# preamp_duo.net
KiCad netlist of a schematic drawn in EAGLE
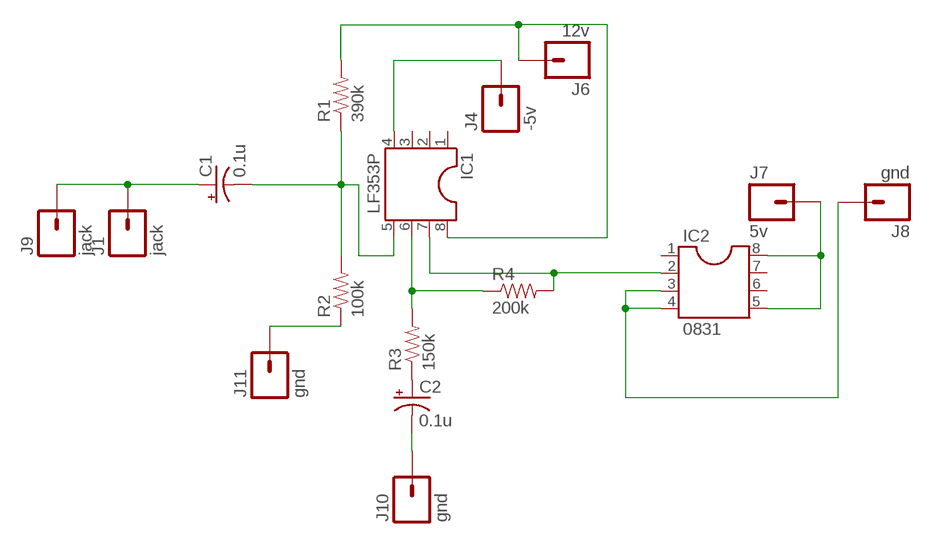
[diagram p0: schematic, sheet 1]

(export (version "E")
  (design (tool "Eeschema 10.0.6"))
  (components
    (comp (ref "C1")
      (value "0.1u")
      (footprint "eagle-import:CPOL-RADIAL-10UF-25V")
      (libsource (lib "eagle-import") (part "CAP_POLPTH2"))
    )
    (comp (ref "C2")
      (value "0.1u")
      (footprint "eagle-import:CPOL-RADIAL-10UF-25V")
      (libsource (lib "eagle-import") (part "CAP_POLPTH2"))
    )
    (comp (ref "IC1")
      (value "LF353P")
      (footprint "eagle-import:DIL08")
      (libsource (lib "eagle-import") (part "DIL8"))
    )
    (comp (ref "IC2")
      (value "0831")
      (footprint "eagle-import:DIL08")
      (libsource (lib "eagle-import") (part "DIL8"))
    )
    (comp (ref "J1")
      (value "jack")
      (footprint "eagle-import:1X01")
      (libsource (lib "eagle-import") (part "M01PTH"))
    )
    (comp (ref "J4")
      (value "-5v")
      (footprint "eagle-import:1X01")
      (libsource (lib "eagle-import") (part "M01PTH"))
    )
    (comp (ref "J6")
      (value "12v")
      (footprint "eagle-import:1X01")
      (libsource (lib "eagle-import") (part "M01PTH"))
    )
    (comp (ref "J7")
      (value "5v")
      (footprint "eagle-import:1X01")
      (libsource (lib "eagle-import") (part "M01PTH"))
    )
    (comp (ref "J8")
      (value "gnd")
      (footprint "eagle-import:1X01")
      (libsource (lib "eagle-import") (part "M01PTH"))
    )
    (comp (ref "J9")
      (value "jack")
      (footprint "eagle-import:1X01")
      (libsource (lib "eagle-import") (part "M01PTH"))
    )
    (comp (ref "J10")
      (value "gnd")
      (footprint "eagle-import:1X01")
      (libsource (lib "eagle-import") (part "M01PTH"))
    )
    (comp (ref "J11")
      (value "gnd")
      (footprint "eagle-import:1X01")
      (libsource (lib "eagle-import") (part "M01PTH"))
    )
    (comp (ref "R1")
      (value "390k")
      (footprint "eagle-import:AXIAL-0.3")
      (libsource (lib "eagle-import") (part "RESISTORAXIAL-0.3"))
    )
    (comp (ref "R2")
      (value "100k")
      (footprint "eagle-import:AXIAL-0.3")
      (libsource (lib "eagle-import") (part "RESISTORAXIAL-0.3"))
    )
    (comp (ref "R3")
      (value "150k")
      (footprint "eagle-import:AXIAL-0.3")
      (libsource (lib "eagle-import") (part "RESISTORAXIAL-0.3"))
    )
    (comp (ref "R4")
      (value "200k")
      (footprint "eagle-import:AXIAL-0.3")
      (libsource (lib "eagle-import") (part "RESISTORAXIAL-0.3"))
    )
  )
  (nets
    (net (code "1") (name "Net-(C1-+)") (class "Default")
      (node (ref "C1") (pin "1") (pinfunction "+_1") (pintype "passive"))
      (node (ref "J1") (pin "1") (pinfunction "1_1") (pintype "passive"))
      (node (ref "J9") (pin "1") (pinfunction "1_1") (pintype "passive"))
    )
    (net (code "2") (name "Net-(C1--)") (class "Default")
      (node (ref "C1") (pin "2") (pinfunction "-_2") (pintype "passive"))
      (node (ref "IC1") (pin "5") (pinfunction "5_5") (pintype "passive"))
      (node (ref "R1") (pin "P$1") (pinfunction "1_P$1") (pintype "passive"))
      (node (ref "R2") (pin "P$2") (pinfunction "2_P$2") (pintype "passive"))
    )
    (net (code "3") (name "Net-(C2-+)") (class "Default")
      (node (ref "C2") (pin "1") (pinfunction "+_1") (pintype "passive"))
      (node (ref "R3") (pin "P$1") (pinfunction "1_P$1") (pintype "passive"))
    )
    (net (code "4") (name "Net-(C2--)") (class "Default")
      (node (ref "C2") (pin "2") (pinfunction "-_2") (pintype "passive"))
      (node (ref "J10") (pin "1") (pinfunction "1_1") (pintype "passive"))
    )
    (net (code "5") (name "Net-(IC1-Pad4)") (class "Default")
      (node (ref "IC1") (pin "4") (pinfunction "4_4") (pintype "passive"))
      (node (ref "J4") (pin "1") (pinfunction "1_1") (pintype "passive"))
    )
    (net (code "6") (name "Net-(IC2-Pad3)") (class "Default")
      (node (ref "IC2") (pin "3") (pinfunction "3_3") (pintype "passive"))
      (node (ref "IC2") (pin "4") (pinfunction "4_4") (pintype "passive"))
      (node (ref "J8") (pin "1") (pinfunction "1_1") (pintype "passive"))
    )
    (net (code "7") (name "Net-(IC2-Pad5)") (class "Default")
      (node (ref "IC2") (pin "5") (pinfunction "5_5") (pintype "passive"))
      (node (ref "IC2") (pin "8") (pinfunction "8_8") (pintype "passive"))
      (node (ref "J7") (pin "1") (pinfunction "1_1") (pintype "passive"))
    )
    (net (code "8") (name "Net-(R1-2)") (class "Default")
      (node (ref "IC1") (pin "8") (pinfunction "8_8") (pintype "passive"))
      (node (ref "J6") (pin "1") (pinfunction "1_1") (pintype "passive"))
      (node (ref "R1") (pin "P$2") (pinfunction "2_P$2") (pintype "passive"))
    )
    (net (code "9") (name "Net-(R2-1)") (class "Default")
      (node (ref "J11") (pin "1") (pinfunction "1_1") (pintype "passive"))
      (node (ref "R2") (pin "P$1") (pinfunction "1_P$1") (pintype "passive"))
    )
    (net (code "10") (name "Net-(R3-2)") (class "Default")
      (node (ref "IC1") (pin "6") (pinfunction "6_6") (pintype "passive"))
      (node (ref "R3") (pin "P$2") (pinfunction "2_P$2") (pintype "passive"))
      (node (ref "R4") (pin "P$1") (pinfunction "1_P$1") (pintype "passive"))
    )
    (net (code "11") (name "Net-(R4-2)") (class "Default")
      (node (ref "IC1") (pin "7") (pinfunction "7_7") (pintype "passive"))
      (node (ref "IC2") (pin "2") (pinfunction "2_2") (pintype "passive"))
      (node (ref "R4") (pin "P$2") (pinfunction "2_P$2") (pintype "passive"))
    )
    (net (code "12") (name "unconnected-(IC1-Pad1)") (class "Default")
      (node (ref "IC1") (pin "1") (pinfunction "1_1") (pintype "passive"))
    )
    (net (code "13") (name "unconnected-(IC1-Pad2)") (class "Default")
      (node (ref "IC1") (pin "2") (pinfunction "2_2") (pintype "passive"))
    )
    (net (code "14") (name "unconnected-(IC1-Pad3)") (class "Default")
      (node (ref "IC1") (pin "3") (pinfunction "3_3") (pintype "passive"))
    )
    (net (code "15") (name "unconnected-(IC2-Pad1)") (class "Default")
      (node (ref "IC2") (pin "1") (pinfunction "1_1") (pintype "passive"))
    )
    (net (code "16") (name "unconnected-(IC2-Pad6)") (class "Default")
      (node (ref "IC2") (pin "6") (pinfunction "6_6") (pintype "passive"))
    )
    (net (code "17") (name "unconnected-(IC2-Pad7)") (class "Default")
      (node (ref "IC2") (pin "7") (pinfunction "7_7") (pintype "passive"))
    )
  )
)
